# HLib-Comm-BLE.net
KiCad netlist of a schematic drawn in Altium Designer
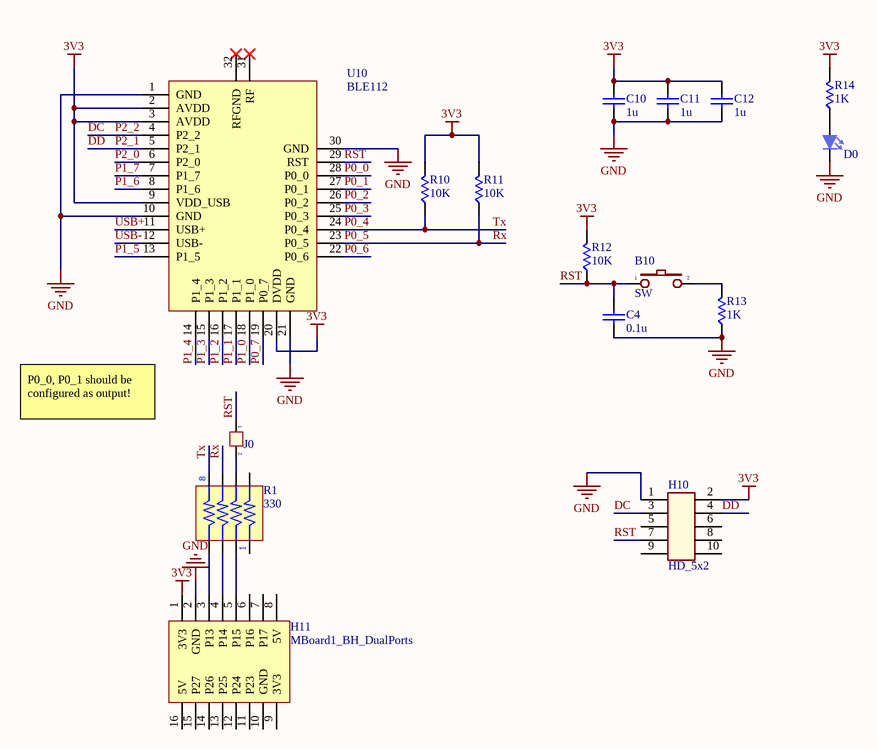
[diagram p0: HLib-Comm-BLE.SchDoc]

(export (version "E")
  (design (tool "Eeschema 10.0.6"))
  (components
    (comp (ref "B10")
      (value "SW")
      (footprint "SW2SMD")
      (description "Switch button 2 pin")
      (libsource (lib "syhaunguyen") (part "SW2"))
    )
    (comp (ref "C4")
      (value "0.1u")
      (footprint "SM_0805_C_CERAMIC")
      (description "Non-polarity ceramic capacitor")
      (fields (field (name "Comment") "C_Ceramic") (field (name "PUBLISHER") "Altium Limited"))
      (libsource (lib "HLib_discrete_sch") (part "C_Ceramic"))
    )
    (comp (ref "C10")
      (value "1u")
      (footprint "SM_0805_C_CERAMIC")
      (description "Non-polarity ceramic capacitor")
      (fields (field (name "Comment") "C_Ceramic") (field (name "PUBLISHER") "Altium Limited"))
      (libsource (lib "HLib_discrete_sch") (part "C_Ceramic"))
    )
    (comp (ref "C11")
      (value "1u")
      (footprint "SM_0805_C_CERAMIC")
      (description "Non-polarity ceramic capacitor")
      (fields (field (name "Comment") "C_Ceramic") (field (name "PUBLISHER") "Altium Limited"))
      (libsource (lib "HLib_discrete_sch") (part "C_Ceramic"))
    )
    (comp (ref "C12")
      (value "1u")
      (footprint "SM_0805_C_CERAMIC")
      (description "Non-polarity ceramic capacitor")
      (fields (field (name "Comment") "C_Ceramic") (field (name "PUBLISHER") "Altium Limited"))
      (libsource (lib "HLib_discrete_sch") (part "C_Ceramic"))
    )
    (comp (ref "D0")
      (value "LED")
      (footprint "SM_0805_LED")
      (fields (field (name "PUBLISHER") "Altium Limited"))
      (libsource (lib "HLib_discrete_sch") (part "LED"))
    )
    (comp (ref "H10")
      (value "HD_5x2")
      (footprint "HD_male_5x2_100mil_straight")
      (description "Header, 5-pins/row, double row,")
      (libsource (lib "HLib_connector_sch") (part "HD_5x2"))
    )
    (comp (ref "H11")
      (value "MBoard1_BH_DualPorts")
      (footprint "MBoard1_BH_DualPorts")
      (libsource (lib "Nhat_Lib") (part "MBoard1_BH_DualPorts"))
    )
    (comp (ref "J0") (value "Jumper 2") (footprint "J2") (libsource (lib "VioletofSun") (part "JP 2")))
    (comp (ref "R1") (value "330") (footprint "RA4") (libsource (lib "Nhat_Lib") (part "RA4")))
    (comp (ref "R10")
      (value "10K")
      (footprint "SM_0805_R")
      (description "Resistor")
      (fields (field (name "Comment") "R") (field (name "PUBLISHER") "Altium Limited"))
      (libsource (lib "HLib_discrete_sch") (part "R"))
    )
    (comp (ref "R11")
      (value "10K")
      (footprint "SM_0805_R")
      (description "Resistor")
      (fields (field (name "Comment") "R") (field (name "PUBLISHER") "Altium Limited"))
      (libsource (lib "HLib_discrete_sch") (part "R"))
    )
    (comp (ref "R12")
      (value "10K")
      (footprint "SM_0805_R")
      (description "Resistor")
      (fields (field (name "Comment") "R") (field (name "PUBLISHER") "Altium Limited"))
      (libsource (lib "HLib_discrete_sch") (part "R"))
    )
    (comp (ref "R13")
      (value "1K")
      (footprint "SM_0805_R")
      (description "Resistor")
      (fields (field (name "Comment") "R") (field (name "PUBLISHER") "Altium Limited"))
      (libsource (lib "HLib_discrete_sch") (part "R"))
    )
    (comp (ref "R14")
      (value "1K")
      (footprint "SM_0805_R")
      (description "Resistor")
      (fields (field (name "Comment") "R") (field (name "PUBLISHER") "Altium Limited"))
      (libsource (lib "HLib_discrete_sch") (part "R"))
    )
    (comp (ref "U10") (value "BLE112") (footprint "BLE112") (libsource (lib "Nhat_Lib") (part "BLE112")))
  )
  (nets
    (net (code "1") (name "/DC") (class "Default")
      (node (ref "H10") (pin "3") (pinfunction "3_3") (pintype "passive"))
      (node (ref "U10") (pin "4") (pinfunction "P2_2_4") (pintype "passive"))
    )
    (net (code "2") (name "/DD") (class "Default")
      (node (ref "H10") (pin "4") (pinfunction "4_4") (pintype "passive"))
      (node (ref "U10") (pin "5") (pinfunction "P2_1_5") (pintype "passive"))
    )
    (net (code "3") (name "/P0_0") (class "Default")
      (node (ref "U10") (pin "28") (pinfunction "P0_0_28") (pintype "passive"))
    )
    (net (code "4") (name "/P0_1") (class "Default")
      (node (ref "U10") (pin "27") (pinfunction "P0_1_27") (pintype "passive"))
    )
    (net (code "5") (name "/P0_2") (class "Default")
      (node (ref "U10") (pin "26") (pinfunction "P0_2_26") (pintype "passive"))
    )
    (net (code "6") (name "/P0_3") (class "Default")
      (node (ref "U10") (pin "25") (pinfunction "P0_3_25") (pintype "passive"))
    )
    (net (code "7") (name "/P0_4") (class "Default")
      (node (ref "R1") (pin "8") (pinfunction "8_8") (pintype "passive"))
      (node (ref "R10") (pin "1") (pinfunction "1_1") (pintype "passive"))
      (node (ref "U10") (pin "24") (pinfunction "P0_4_24") (pintype "passive"))
    )
    (net (code "8") (name "/P0_5") (class "Default")
      (node (ref "R1") (pin "6") (pinfunction "6_6") (pintype "passive"))
      (node (ref "R11") (pin "1") (pinfunction "1_1") (pintype "passive"))
      (node (ref "U10") (pin "23") (pinfunction "P0_5_23") (pintype "passive"))
    )
    (net (code "9") (name "/P0_6") (class "Default")
      (node (ref "U10") (pin "22") (pinfunction "P0_6_22") (pintype "passive"))
    )
    (net (code "10") (name "/P0_7") (class "Default")
      (node (ref "U10") (pin "19") (pinfunction "P0_7_19") (pintype "passive"))
    )
    (net (code "11") (name "/P1_0") (class "Default")
      (node (ref "U10") (pin "18") (pinfunction "P1_0_18") (pintype "passive"))
    )
    (net (code "12") (name "/P1_1") (class "Default")
      (node (ref "U10") (pin "17") (pinfunction "P1_1_17") (pintype "passive"))
    )
    (net (code "13") (name "/P1_2") (class "Default")
      (node (ref "U10") (pin "16") (pinfunction "P1_2_16") (pintype "passive"))
    )
    (net (code "14") (name "/P1_3") (class "Default")
      (node (ref "U10") (pin "15") (pinfunction "P1_3_15") (pintype "passive"))
    )
    (net (code "15") (name "/P1_4") (class "Default")
      (node (ref "U10") (pin "14") (pinfunction "P1_4_14") (pintype "passive"))
    )
    (net (code "16") (name "/P1_5") (class "Default")
      (node (ref "U10") (pin "13") (pinfunction "P1_5_13") (pintype "passive"))
    )
    (net (code "17") (name "/P1_6") (class "Default")
      (node (ref "U10") (pin "8") (pinfunction "P1_6_8") (pintype "passive"))
    )
    (net (code "18") (name "/P1_7") (class "Default")
      (node (ref "U10") (pin "7") (pinfunction "P1_7_7") (pintype "passive"))
    )
    (net (code "19") (name "/P2_0") (class "Default")
      (node (ref "U10") (pin "6") (pinfunction "P2_0_6") (pintype "passive"))
    )
    (net (code "20") (name "/RST") (class "Default")
      (node (ref "B10") (pin "1") (pinfunction "1_1") (pintype "passive"))
      (node (ref "C4") (pin "2") (pinfunction "2_2") (pintype "passive"))
      (node (ref "H10") (pin "7") (pinfunction "7_7") (pintype "passive"))
      (node (ref "J0") (pin "1") (pinfunction "1_1") (pintype "passive"))
      (node (ref "R12") (pin "1") (pinfunction "1_1") (pintype "passive"))
      (node (ref "U10") (pin "29") (pinfunction "RST_29") (pintype "passive"))
    )
    (net (code "21") (name "/USB+") (class "Default")
      (node (ref "U10") (pin "11") (pinfunction "USB+_11") (pintype "passive"))
    )
    (net (code "22") (name "/USB-") (class "Default")
      (node (ref "U10") (pin "12") (pinfunction "USB-_12") (pintype "passive"))
    )
    (net (code "23") (name "3V3") (class "Default")
      (node (ref "C10") (pin "2") (pinfunction "2_2") (pintype "passive"))
      (node (ref "C11") (pin "2") (pinfunction "2_2") (pintype "passive"))
      (node (ref "C12") (pin "2") (pinfunction "2_2") (pintype "passive"))
      (node (ref "H10") (pin "2") (pinfunction "2_2") (pintype "passive"))
      (node (ref "H11") (pin "1") (pinfunction "3V3_1") (pintype "passive"))
      (node (ref "R10") (pin "2") (pinfunction "2_2") (pintype "passive"))
      (node (ref "R11") (pin "2") (pinfunction "2_2") (pintype "passive"))
      (node (ref "R12") (pin "2") (pinfunction "2_2") (pintype "passive"))
      (node (ref "R14") (pin "2") (pinfunction "2_2") (pintype "passive"))
      (node (ref "U10") (pin "2") (pinfunction "AVDD_2") (pintype "passive"))
      (node (ref "U10") (pin "20") (pinfunction "DVDD_20") (pintype "passive"))
      (node (ref "U10") (pin "3") (pinfunction "AVDD_3") (pintype "passive"))
      (node (ref "U10") (pin "9") (pinfunction "VDD_USB_9") (pintype "passive"))
    )
    (net (code "24") (name "GND") (class "Default")
      (node (ref "C10") (pin "1") (pinfunction "1_1") (pintype "passive"))
      (node (ref "C11") (pin "1") (pinfunction "1_1") (pintype "passive"))
      (node (ref "C12") (pin "1") (pinfunction "1_1") (pintype "passive"))
      (node (ref "C4") (pin "1") (pinfunction "1_1") (pintype "passive"))
      (node (ref "D0") (pin "2") (pinfunction "K_2") (pintype "passive"))
      (node (ref "H10") (pin "1") (pinfunction "1_1") (pintype "passive"))
      (node (ref "H11") (pin "2") (pinfunction "GND_2") (pintype "passive"))
      (node (ref "R13") (pin "1") (pinfunction "1_1") (pintype "passive"))
      (node (ref "U10") (pin "1") (pinfunction "GND_1") (pintype "passive"))
      (node (ref "U10") (pin "10") (pinfunction "GND_10") (pintype "passive"))
      (node (ref "U10") (pin "21") (pinfunction "GND_21") (pintype "passive"))
      (node (ref "U10") (pin "30") (pinfunction "GND_30") (pintype "passive"))
    )
    (net (code "25") (name "Net-(B10-Pad2)") (class "Default")
      (node (ref "B10") (pin "2") (pinfunction "2_2") (pintype "passive"))
      (node (ref "R13") (pin "2") (pinfunction "2_2") (pintype "passive"))
    )
    (net (code "26") (name "Net-(D0-A)") (class "Default")
      (node (ref "D0") (pin "1") (pinfunction "A_1") (pintype "passive"))
      (node (ref "R14") (pin "1") (pinfunction "1_1") (pintype "passive"))
    )
    (net (code "27") (name "Net-(H11-P13)") (class "Default")
      (node (ref "H11") (pin "3") (pinfunction "P13_3") (pintype "passive"))
      (node (ref "R1") (pin "7") (pinfunction "7_7") (pintype "passive"))
    )
    (net (code "28") (name "Net-(H11-P14)") (class "Default")
      (node (ref "H11") (pin "4") (pinfunction "P14_4") (pintype "passive"))
      (node (ref "R1") (pin "5") (pinfunction "5_5") (pintype "passive"))
    )
    (net (code "29") (name "Net-(H11-P15)") (class "Default")
      (node (ref "H11") (pin "5") (pinfunction "P15_5") (pintype "passive"))
      (node (ref "R1") (pin "3") (pinfunction "3_3") (pintype "passive"))
    )
    (net (code "30") (name "Net-(J0-Pad2)") (class "Default")
      (node (ref "J0") (pin "2") (pinfunction "2_2") (pintype "passive"))
      (node (ref "R1") (pin "4") (pinfunction "4_4") (pintype "passive"))
    )
    (net (code "31") (name "unconnected-(H10-Pad5)") (class "Default")
      (node (ref "H10") (pin "5") (pinfunction "5_5") (pintype "passive"))
    )
    (net (code "32") (name "unconnected-(H10-Pad6)") (class "Default")
      (node (ref "H10") (pin "6") (pinfunction "6_6") (pintype "passive"))
    )
    (net (code "33") (name "unconnected-(H10-Pad8)") (class "Default")
      (node (ref "H10") (pin "8") (pinfunction "8_8") (pintype "passive"))
    )
    (net (code "34") (name "unconnected-(H10-Pad9)") (class "Default")
      (node (ref "H10") (pin "9") (pinfunction "9_9") (pintype "passive"))
    )
    (net (code "35") (name "unconnected-(H10-Pad10)") (class "Default")
      (node (ref "H10") (pin "10") (pinfunction "10_10") (pintype "passive"))
    )
    (net (code "36") (name "unconnected-(H11-3V3-Pad9)") (class "Default")
      (node (ref "H11") (pin "9") (pinfunction "3V3_9") (pintype "passive"))
    )
    (net (code "37") (name "unconnected-(H11-5V-Pad8)") (class "Default")
      (node (ref "H11") (pin "8") (pinfunction "5V_8") (pintype "passive"))
    )
    (net (code "38") (name "unconnected-(H11-5V-Pad16)") (class "Default")
      (node (ref "H11") (pin "16") (pinfunction "5V_16") (pintype "passive"))
    )
    (net (code "39") (name "unconnected-(H11-GND-Pad10)") (class "Default")
      (node (ref "H11") (pin "10") (pinfunction "GND_10") (pintype "passive"))
    )
    (net (code "40") (name "unconnected-(H11-P16-Pad6)") (class "Default")
      (node (ref "H11") (pin "6") (pinfunction "P16_6") (pintype "passive"))
    )
    (net (code "41") (name "unconnected-(H11-P17-Pad7)") (class "Default")
      (node (ref "H11") (pin "7") (pinfunction "P17_7") (pintype "passive"))
    )
    (net (code "42") (name "unconnected-(H11-P23-Pad11)") (class "Default")
      (node (ref "H11") (pin "11") (pinfunction "P23_11") (pintype "passive"))
    )
    (net (code "43") (name "unconnected-(H11-P24-Pad12)") (class "Default")
      (node (ref "H11") (pin "12") (pinfunction "P24_12") (pintype "passive"))
    )
    (net (code "44") (name "unconnected-(H11-P25-Pad13)") (class "Default")
      (node (ref "H11") (pin "13") (pinfunction "P25_13") (pintype "passive"))
    )
    (net (code "45") (name "unconnected-(H11-P26-Pad14)") (class "Default")
      (node (ref "H11") (pin "14") (pinfunction "P26_14") (pintype "passive"))
    )
    (net (code "46") (name "unconnected-(H11-P27-Pad15)") (class "Default")
      (node (ref "H11") (pin "15") (pinfunction "P27_15") (pintype "passive"))
    )
    (net (code "47") (name "unconnected-(R1-Pad1)") (class "Default")
      (node (ref "R1") (pin "1") (pinfunction "1_1") (pintype "passive"))
    )
    (net (code "48") (name "unconnected-(R1-Pad2)") (class "Default")
      (node (ref "R1") (pin "2") (pinfunction "2_2") (pintype "passive"))
    )
    (net (code "49") (name "unconnected-(U10-RF-Pad31)") (class "Default")
      (node (ref "U10") (pin "31") (pinfunction "RF_31") (pintype "passive+no_connect"))
    )
    (net (code "50") (name "unconnected-(U10-RFGND-Pad32)") (class "Default")
      (node (ref "U10") (pin "32") (pinfunction "RFGND_32") (pintype "passive+no_connect"))
    )
  )
)
